# Mimi_layout_logo.net
KiCad netlist of a schematic drawn in EAGLE
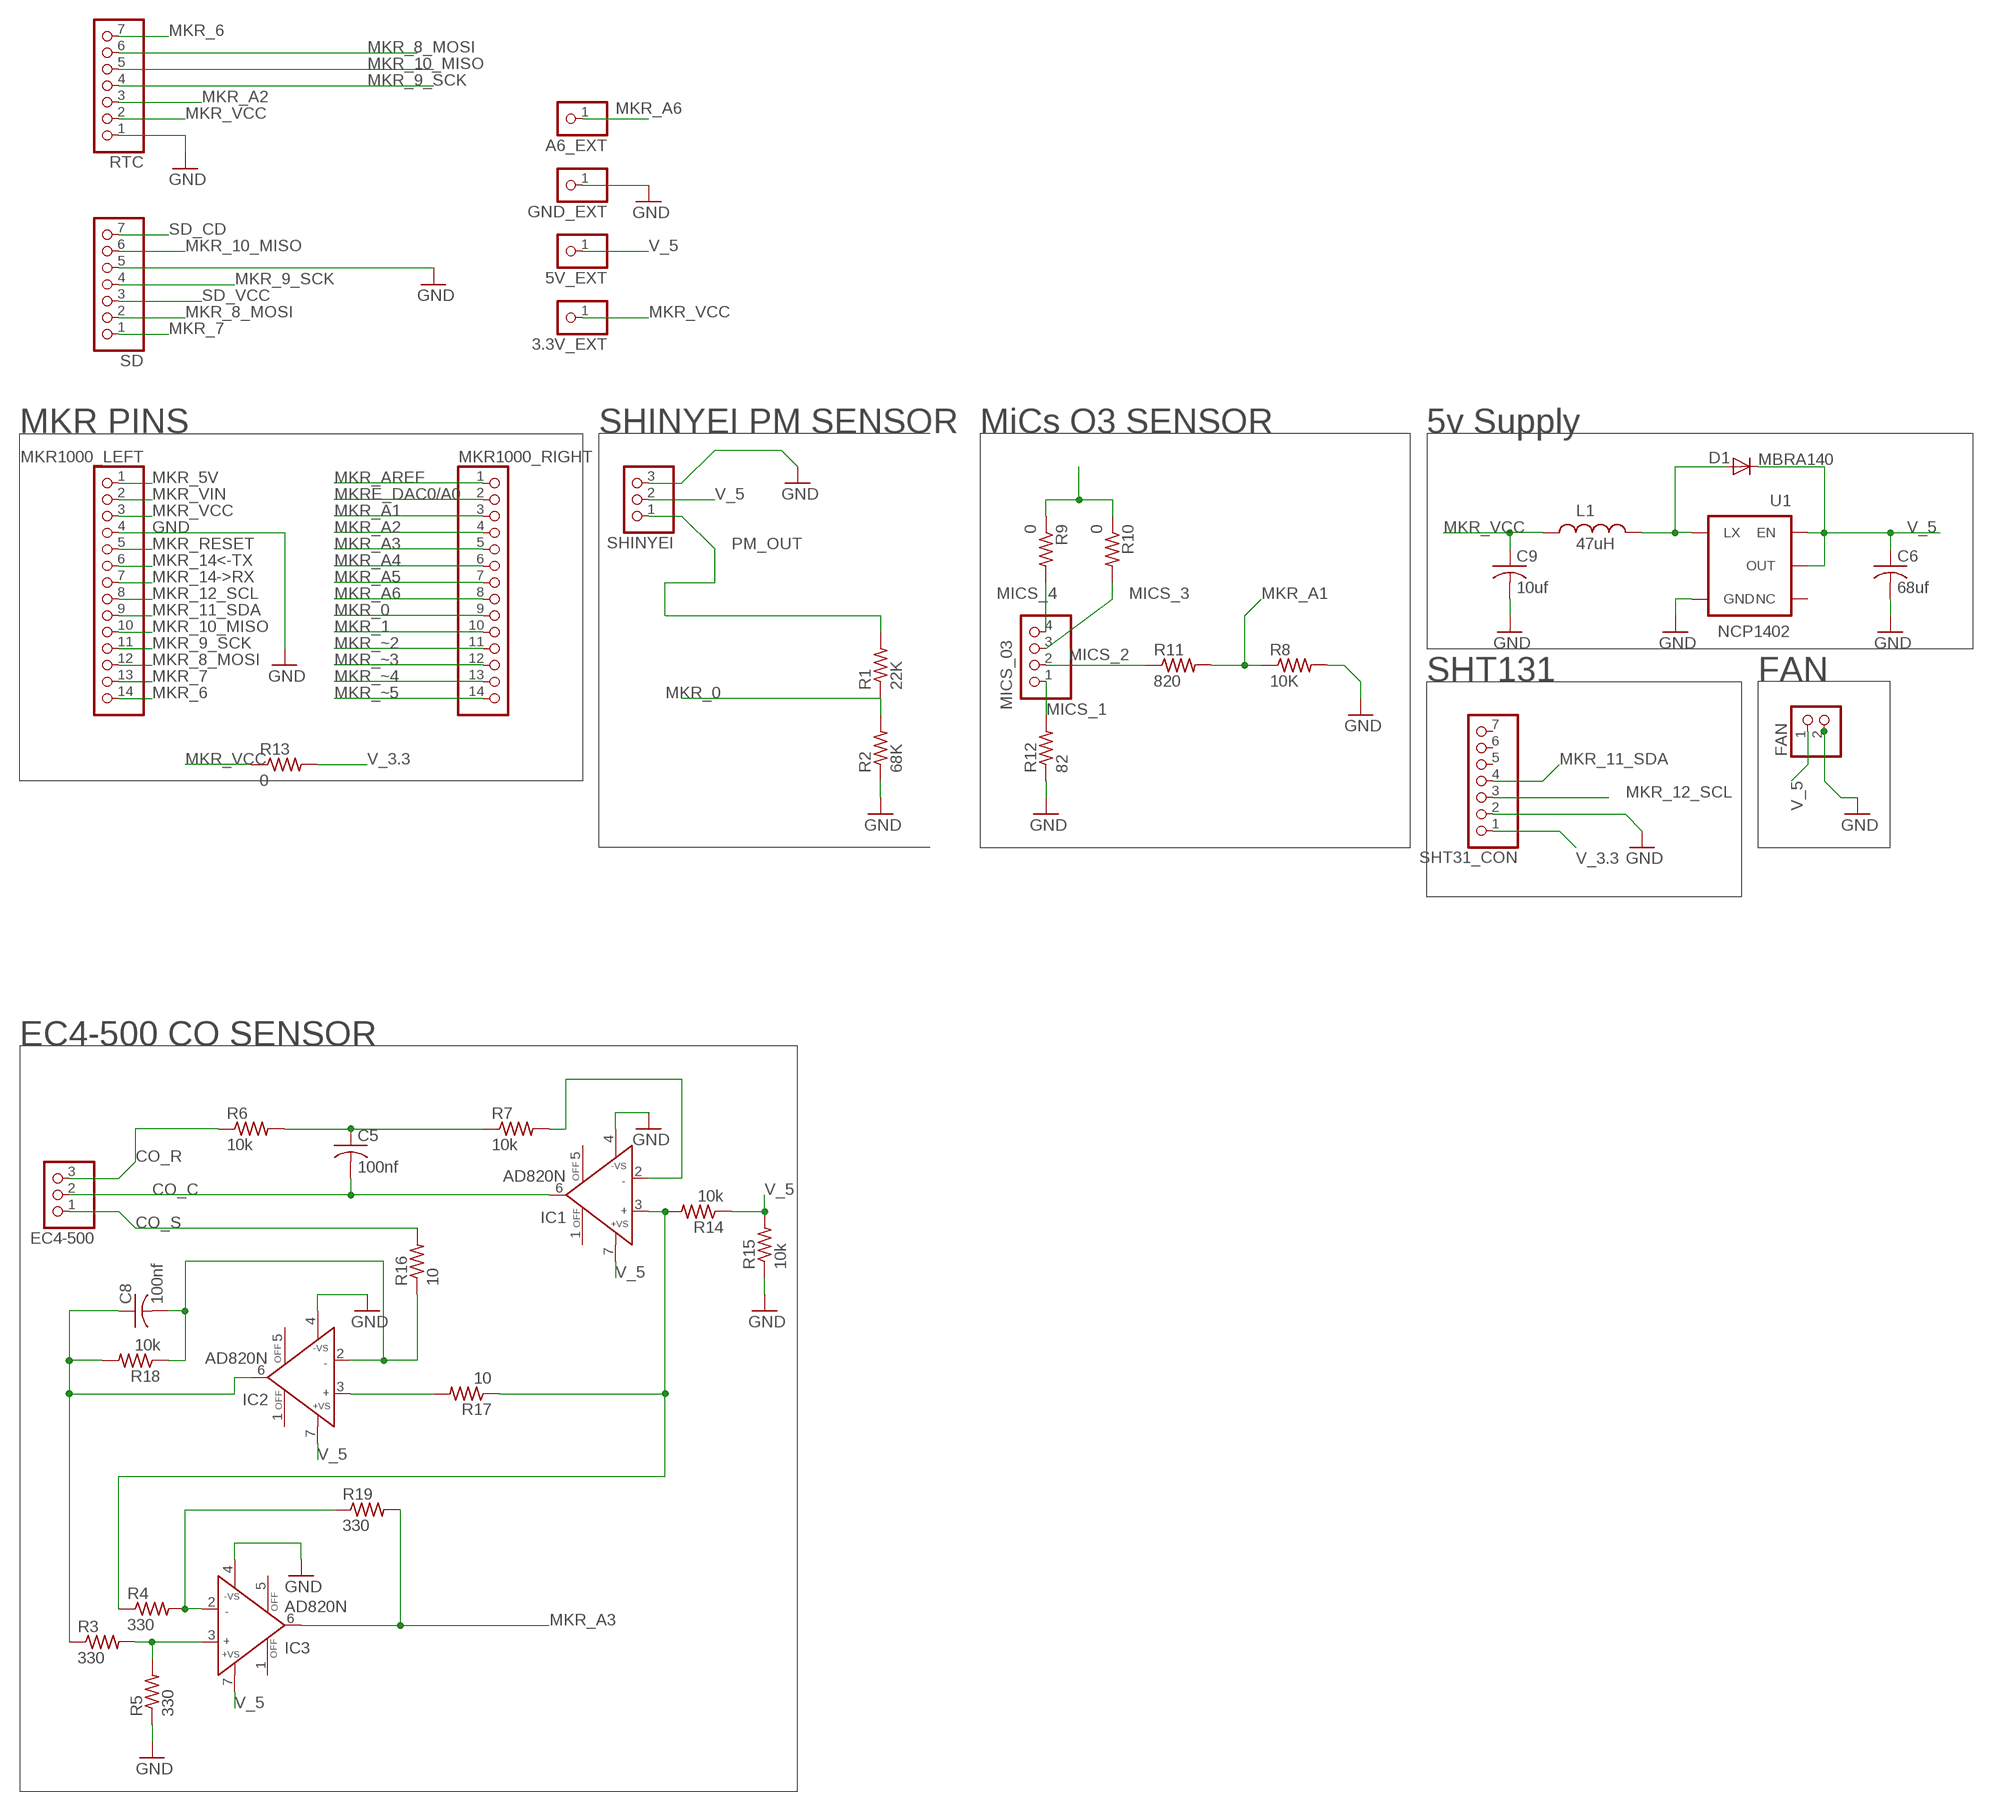
[diagram p0: schematic, sheet 1]

(export (version "E")
  (design (tool "Eeschema 10.0.6"))
  (components
    (comp (ref "3.3V_EXT")
      (value "PINHD-1X1")
      (footprint "eagle-import:1X01")
      (libsource (lib "eagle-import") (part "PINHD-1X1"))
    )
    (comp (ref "5V_EXT")
      (value "PINHD-1X1")
      (footprint "eagle-import:1X01")
      (libsource (lib "eagle-import") (part "PINHD-1X1"))
    )
    (comp (ref "A6_EXT")
      (value "PINHD-1X1")
      (footprint "eagle-import:1X01")
      (libsource (lib "eagle-import") (part "PINHD-1X1"))
    )
    (comp (ref "C5")
      (value "100nf")
      (footprint "eagle-import:C0805")
      (libsource (lib "eagle-import") (part "C-USC0805"))
    )
    (comp (ref "C6")
      (value "68uf")
      (footprint "eagle-import:C0805")
      (libsource (lib "eagle-import") (part "C-USC0805"))
    )
    (comp (ref "C8")
      (value "100nf")
      (footprint "eagle-import:C0805")
      (libsource (lib "eagle-import") (part "C-USC0805"))
    )
    (comp (ref "C9")
      (value "10uf")
      (footprint "eagle-import:C0805")
      (libsource (lib "eagle-import") (part "C-USC0805"))
    )
    (comp (ref "D1")
      (value "MBRA140")
      (footprint "eagle-import:SMA-DIODE")
      (libsource (lib "eagle-import") (part "DIODESMA"))
    )
    (comp (ref "EC4-500")
      (value "PINHD-1X3")
      (footprint "eagle-import:1X03")
      (libsource (lib "eagle-import") (part "PINHD-1X3"))
    )
    (comp (ref "FAN")
      (value "PINHD-1X2")
      (footprint "eagle-import:1X02")
      (libsource (lib "eagle-import") (part "PINHD-1X2"))
    )
    (comp (ref "GND_EXT")
      (value "PINHD-1X1")
      (footprint "eagle-import:1X01")
      (libsource (lib "eagle-import") (part "PINHD-1X1"))
    )
    (comp (ref "IC1")
      (value "AD820N")
      (footprint "eagle-import:DIL08")
      (libsource (lib "eagle-import") (part "AD820N"))
    )
    (comp (ref "IC2")
      (value "AD820N")
      (footprint "eagle-import:DIL08")
      (libsource (lib "eagle-import") (part "AD820N"))
    )
    (comp (ref "IC3")
      (value "AD820N")
      (footprint "eagle-import:DIL08")
      (libsource (lib "eagle-import") (part "AD820N"))
    )
    (comp (ref "L1")
      (value "47uH")
      (footprint "eagle-import:CR54")
      (libsource (lib "eagle-import") (part "INDUCTORCR54"))
    )
    (comp (ref "MICS_03")
      (value "PINHD-1X4")
      (footprint "eagle-import:1X04")
      (libsource (lib "eagle-import") (part "PINHD-1X4"))
    )
    (comp (ref "MKR1000_LEFT")
      (value "PINHD-1X14")
      (footprint "eagle-import:1X14")
      (libsource (lib "eagle-import") (part "PINHD-1X14"))
    )
    (comp (ref "MKR1000_RIGHT")
      (value "PINHD-1X14")
      (footprint "eagle-import:1X14")
      (libsource (lib "eagle-import") (part "PINHD-1X14"))
    )
    (comp (ref "R1")
      (value "22K")
      (footprint "eagle-import:R0805")
      (libsource (lib "eagle-import") (part "R-US_R0805"))
    )
    (comp (ref "R2")
      (value "68K")
      (footprint "eagle-import:R0805")
      (libsource (lib "eagle-import") (part "R-US_R0805"))
    )
    (comp (ref "R3")
      (value "330")
      (footprint "eagle-import:R0805")
      (libsource (lib "eagle-import") (part "R-US_R0805"))
    )
    (comp (ref "R4")
      (value "330")
      (footprint "eagle-import:R0805")
      (libsource (lib "eagle-import") (part "R-US_R0805"))
    )
    (comp (ref "R5")
      (value "330")
      (footprint "eagle-import:R0805")
      (libsource (lib "eagle-import") (part "R-US_R0805"))
    )
    (comp (ref "R6")
      (value "10k")
      (footprint "eagle-import:R0805")
      (libsource (lib "eagle-import") (part "R-US_R0805"))
    )
    (comp (ref "R7")
      (value "10k")
      (footprint "eagle-import:R0805")
      (libsource (lib "eagle-import") (part "R-US_R0805"))
    )
    (comp (ref "R8")
      (value "10K")
      (footprint "eagle-import:R0805")
      (libsource (lib "eagle-import") (part "R-US_R0805"))
    )
    (comp (ref "R9")
      (value "0")
      (footprint "eagle-import:R0805")
      (libsource (lib "eagle-import") (part "R-US_R0805"))
    )
    (comp (ref "R10")
      (value "0")
      (footprint "eagle-import:R0805")
      (libsource (lib "eagle-import") (part "R-US_R0805"))
    )
    (comp (ref "R11")
      (value "820")
      (footprint "eagle-import:R0805")
      (libsource (lib "eagle-import") (part "R-US_R0805"))
    )
    (comp (ref "R12")
      (value "82")
      (footprint "eagle-import:R0805")
      (libsource (lib "eagle-import") (part "R-US_R0805"))
    )
    (comp (ref "R13")
      (value "0")
      (footprint "eagle-import:R0805")
      (libsource (lib "eagle-import") (part "R-US_R0805"))
    )
    (comp (ref "R14")
      (value "10k")
      (footprint "eagle-import:R0805")
      (libsource (lib "eagle-import") (part "R-US_R0805"))
    )
    (comp (ref "R15")
      (value "10k")
      (footprint "eagle-import:R0805")
      (libsource (lib "eagle-import") (part "R-US_R0805"))
    )
    (comp (ref "R16")
      (value "10")
      (footprint "eagle-import:R0805")
      (libsource (lib "eagle-import") (part "R-US_R0805"))
    )
    (comp (ref "R17")
      (value "10")
      (footprint "eagle-import:R0805")
      (libsource (lib "eagle-import") (part "R-US_R0805"))
    )
    (comp (ref "R18")
      (value "10k")
      (footprint "eagle-import:R0805")
      (libsource (lib "eagle-import") (part "R-US_R0805"))
    )
    (comp (ref "R19")
      (value "330")
      (footprint "eagle-import:R0805")
      (libsource (lib "eagle-import") (part "R-US_R0805"))
    )
    (comp (ref "RTC")
      (value "PINHD-1X7")
      (footprint "eagle-import:1X07")
      (libsource (lib "eagle-import") (part "PINHD-1X7"))
    )
    (comp (ref "SD")
      (value "PINHD-1X7")
      (footprint "eagle-import:1X07")
      (libsource (lib "eagle-import") (part "PINHD-1X7"))
    )
    (comp (ref "SHINYEI")
      (value "PINHD-1X3")
      (footprint "eagle-import:1X03")
      (libsource (lib "eagle-import") (part "PINHD-1X3"))
    )
    (comp (ref "SHT31_CON")
      (value "PINHD-1X7")
      (footprint "eagle-import:1X07")
      (libsource (lib "eagle-import") (part "PINHD-1X7"))
    )
    (comp (ref "U1")
      (value "NCP1402")
      (footprint "eagle-import:SOT23-5")
      (libsource (lib "eagle-import") (part "V_REG_NCP1400SOT23-5"))
    )
  )
  (nets
    (net (code "1") (name "/CO_C") (class "Default")
      (node (ref "C5") (pin "2") (pinfunction "2_2") (pintype "passive"))
      (node (ref "EC4-500") (pin "2") (pinfunction "2_2") (pintype "passive"))
      (node (ref "IC1") (pin "6") (pinfunction "OUT_6") (pintype "output"))
    )
    (net (code "2") (name "/CO_R") (class "Default")
      (node (ref "EC4-500") (pin "3") (pinfunction "3_3") (pintype "passive"))
      (node (ref "R6") (pin "1") (pinfunction "1_1") (pintype "passive"))
    )
    (net (code "3") (name "/CO_S") (class "Default")
      (node (ref "EC4-500") (pin "1") (pinfunction "1_1") (pintype "passive"))
      (node (ref "R16") (pin "2") (pinfunction "2_2") (pintype "passive"))
    )
    (net (code "4") (name "/MICS_1") (class "Default")
      (node (ref "MICS_03") (pin "1") (pinfunction "1_1") (pintype "passive"))
      (node (ref "R12") (pin "2") (pinfunction "2_2") (pintype "passive"))
    )
    (net (code "5") (name "/MICS_2") (class "Default")
      (node (ref "MICS_03") (pin "2") (pinfunction "2_2") (pintype "passive"))
      (node (ref "R11") (pin "1") (pinfunction "1_1") (pintype "passive"))
    )
    (net (code "6") (name "/MICS_3") (class "Default")
      (node (ref "MICS_03") (pin "3") (pinfunction "3_3") (pintype "passive"))
      (node (ref "R10") (pin "2") (pinfunction "2_2") (pintype "passive"))
    )
    (net (code "7") (name "/MICS_4") (class "Default")
      (node (ref "MICS_03") (pin "4") (pinfunction "4_4") (pintype "passive"))
      (node (ref "R9") (pin "2") (pinfunction "2_2") (pintype "passive"))
    )
    (net (code "8") (name "/MKRE_DAC0{slash}A0") (class "Default")
      (node (ref "MKR1000_RIGHT") (pin "2") (pinfunction "2_2") (pintype "passive"))
    )
    (net (code "9") (name "/MKR_0") (class "Default")
      (node (ref "MKR1000_RIGHT") (pin "9") (pinfunction "9_9") (pintype "passive"))
      (node (ref "R1") (pin "1") (pinfunction "1_1") (pintype "passive"))
      (node (ref "R2") (pin "2") (pinfunction "2_2") (pintype "passive"))
    )
    (net (code "10") (name "/MKR_1") (class "Default")
      (node (ref "MKR1000_RIGHT") (pin "10") (pinfunction "10_10") (pintype "passive"))
    )
    (net (code "11") (name "/MKR_5V") (class "Default")
      (node (ref "MKR1000_LEFT") (pin "1") (pinfunction "1_1") (pintype "passive"))
    )
    (net (code "12") (name "/MKR_6") (class "Default")
      (node (ref "MKR1000_LEFT") (pin "14") (pinfunction "14_14") (pintype "passive"))
      (node (ref "RTC") (pin "7") (pinfunction "7_7") (pintype "passive"))
    )
    (net (code "13") (name "/MKR_7") (class "Default")
      (node (ref "MKR1000_LEFT") (pin "13") (pinfunction "13_13") (pintype "passive"))
      (node (ref "SD") (pin "1") (pinfunction "1_1") (pintype "passive"))
    )
    (net (code "14") (name "/MKR_8_MOSI") (class "Default")
      (node (ref "MKR1000_LEFT") (pin "12") (pinfunction "12_12") (pintype "passive"))
      (node (ref "RTC") (pin "6") (pinfunction "6_6") (pintype "passive"))
      (node (ref "SD") (pin "2") (pinfunction "2_2") (pintype "passive"))
    )
    (net (code "15") (name "/MKR_9_SCK") (class "Default")
      (node (ref "MKR1000_LEFT") (pin "11") (pinfunction "11_11") (pintype "passive"))
      (node (ref "RTC") (pin "4") (pinfunction "4_4") (pintype "passive"))
      (node (ref "SD") (pin "4") (pinfunction "4_4") (pintype "passive"))
    )
    (net (code "16") (name "/MKR_10_MISO") (class "Default")
      (node (ref "MKR1000_LEFT") (pin "10") (pinfunction "10_10") (pintype "passive"))
      (node (ref "RTC") (pin "5") (pinfunction "5_5") (pintype "passive"))
      (node (ref "SD") (pin "6") (pinfunction "6_6") (pintype "passive"))
    )
    (net (code "17") (name "/MKR_11_SDA") (class "Default")
      (node (ref "MKR1000_LEFT") (pin "9") (pinfunction "9_9") (pintype "passive"))
      (node (ref "SHT31_CON") (pin "4") (pinfunction "4_4") (pintype "passive"))
    )
    (net (code "18") (name "/MKR_12_SCL") (class "Default")
      (node (ref "MKR1000_LEFT") (pin "8") (pinfunction "8_8") (pintype "passive"))
      (node (ref "SHT31_CON") (pin "3") (pinfunction "3_3") (pintype "passive"))
    )
    (net (code "19") (name "/MKR_14->RX") (class "Default")
      (node (ref "MKR1000_LEFT") (pin "7") (pinfunction "7_7") (pintype "passive"))
    )
    (net (code "20") (name "/MKR_14<-TX") (class "Default")
      (node (ref "MKR1000_LEFT") (pin "6") (pinfunction "6_6") (pintype "passive"))
    )
    (net (code "21") (name "/MKR_A1") (class "Default")
      (node (ref "MKR1000_RIGHT") (pin "3") (pinfunction "3_3") (pintype "passive"))
      (node (ref "R11") (pin "2") (pinfunction "2_2") (pintype "passive"))
      (node (ref "R8") (pin "1") (pinfunction "1_1") (pintype "passive"))
    )
    (net (code "22") (name "/MKR_A2") (class "Default")
      (node (ref "MKR1000_RIGHT") (pin "4") (pinfunction "4_4") (pintype "passive"))
      (node (ref "RTC") (pin "3") (pinfunction "3_3") (pintype "passive"))
    )
    (net (code "23") (name "/MKR_A3") (class "Default")
      (node (ref "IC3") (pin "6") (pinfunction "OUT_6") (pintype "output"))
      (node (ref "MKR1000_RIGHT") (pin "5") (pinfunction "5_5") (pintype "passive"))
      (node (ref "R19") (pin "2") (pinfunction "2_2") (pintype "passive"))
    )
    (net (code "24") (name "/MKR_A4") (class "Default")
      (node (ref "MKR1000_RIGHT") (pin "6") (pinfunction "6_6") (pintype "passive"))
    )
    (net (code "25") (name "/MKR_A5") (class "Default")
      (node (ref "MKR1000_RIGHT") (pin "7") (pinfunction "7_7") (pintype "passive"))
    )
    (net (code "26") (name "/MKR_A6") (class "Default")
      (node (ref "A6_EXT") (pin "1") (pinfunction "1_1") (pintype "passive"))
      (node (ref "MKR1000_RIGHT") (pin "8") (pinfunction "8_8") (pintype "passive"))
    )
    (net (code "27") (name "/MKR_AREF") (class "Default")
      (node (ref "MKR1000_RIGHT") (pin "1") (pinfunction "1_1") (pintype "passive"))
    )
    (net (code "28") (name "/MKR_RESET") (class "Default")
      (node (ref "MKR1000_LEFT") (pin "5") (pinfunction "5_5") (pintype "passive"))
    )
    (net (code "29") (name "/MKR_VCC") (class "Default")
      (node (ref "3.3V_EXT") (pin "1") (pinfunction "1_1") (pintype "passive"))
      (node (ref "C9") (pin "1") (pinfunction "1_1") (pintype "passive"))
      (node (ref "L1") (pin "P$1") (pinfunction "1_P$1") (pintype "passive"))
      (node (ref "MKR1000_LEFT") (pin "3") (pinfunction "3_3") (pintype "passive"))
      (node (ref "R13") (pin "1") (pinfunction "1_1") (pintype "passive"))
      (node (ref "RTC") (pin "2") (pinfunction "2_2") (pintype "passive"))
    )
    (net (code "30") (name "/MKR_VIN") (class "Default")
      (node (ref "MKR1000_LEFT") (pin "2") (pinfunction "2_2") (pintype "passive"))
    )
    (net (code "31") (name "/MKR_~{2}") (class "Default")
      (node (ref "MKR1000_RIGHT") (pin "11") (pinfunction "11_11") (pintype "passive"))
    )
    (net (code "32") (name "/MKR_~{3}") (class "Default")
      (node (ref "MKR1000_RIGHT") (pin "12") (pinfunction "12_12") (pintype "passive"))
    )
    (net (code "33") (name "/MKR_~{4}") (class "Default")
      (node (ref "MKR1000_RIGHT") (pin "13") (pinfunction "13_13") (pintype "passive"))
    )
    (net (code "34") (name "/MKR_~{5}") (class "Default")
      (node (ref "MKR1000_RIGHT") (pin "14") (pinfunction "14_14") (pintype "passive"))
    )
    (net (code "35") (name "/PM_OUT") (class "Default")
      (node (ref "R1") (pin "2") (pinfunction "2_2") (pintype "passive"))
      (node (ref "SHINYEI") (pin "1") (pinfunction "1_1") (pintype "passive"))
    )
    (net (code "36") (name "/SD_CD") (class "Default")
      (node (ref "SD") (pin "7") (pinfunction "7_7") (pintype "passive"))
    )
    (net (code "37") (name "/SD_VCC") (class "Default")
      (node (ref "SD") (pin "3") (pinfunction "3_3") (pintype "passive"))
    )
    (net (code "38") (name "/V_3.3") (class "Default")
      (node (ref "R13") (pin "2") (pinfunction "2_2") (pintype "passive"))
      (node (ref "SHT31_CON") (pin "1") (pinfunction "1_1") (pintype "passive"))
    )
    (net (code "39") (name "/V_5") (class "Default")
      (node (ref "5V_EXT") (pin "1") (pinfunction "1_1") (pintype "passive"))
      (node (ref "C6") (pin "1") (pinfunction "1_1") (pintype "passive"))
      (node (ref "D1") (pin "C") (pinfunction "C_C") (pintype "passive"))
      (node (ref "FAN") (pin "1") (pinfunction "1_1") (pintype "passive"))
      (node (ref "IC1") (pin "7") (pinfunction "+VS_7") (pintype "input"))
      (node (ref "IC2") (pin "7") (pinfunction "+VS_7") (pintype "input"))
      (node (ref "IC3") (pin "7") (pinfunction "+VS_7") (pintype "input"))
      (node (ref "R10") (pin "1") (pinfunction "1_1") (pintype "passive"))
      (node (ref "R14") (pin "1") (pinfunction "1_1") (pintype "passive"))
      (node (ref "R15") (pin "2") (pinfunction "2_2") (pintype "passive"))
      (node (ref "R9") (pin "1") (pinfunction "1_1") (pintype "passive"))
      (node (ref "SHINYEI") (pin "2") (pinfunction "2_2") (pintype "passive"))
      (node (ref "U1") (pin "1") (pinfunction "EN_1") (pintype "input"))
      (node (ref "U1") (pin "2") (pinfunction "OUT_2") (pintype "passive"))
    )
    (net (code "40") (name "GND") (class "Default")
      (node (ref "C6") (pin "2") (pinfunction "2_2") (pintype "passive"))
      (node (ref "C9") (pin "2") (pinfunction "2_2") (pintype "passive"))
      (node (ref "FAN") (pin "2") (pinfunction "2_2") (pintype "passive"))
      (node (ref "GND_EXT") (pin "1") (pinfunction "1_1") (pintype "passive"))
      (node (ref "IC1") (pin "4") (pinfunction "-VS_4") (pintype "input"))
      (node (ref "IC2") (pin "4") (pinfunction "-VS_4") (pintype "input"))
      (node (ref "IC3") (pin "4") (pinfunction "-VS_4") (pintype "input"))
      (node (ref "MKR1000_LEFT") (pin "4") (pinfunction "4_4") (pintype "passive"))
      (node (ref "R12") (pin "1") (pinfunction "1_1") (pintype "passive"))
      (node (ref "R15") (pin "1") (pinfunction "1_1") (pintype "passive"))
      (node (ref "R2") (pin "1") (pinfunction "1_1") (pintype "passive"))
      (node (ref "R5") (pin "1") (pinfunction "1_1") (pintype "passive"))
      (node (ref "R8") (pin "2") (pinfunction "2_2") (pintype "passive"))
      (node (ref "RTC") (pin "1") (pinfunction "1_1") (pintype "passive"))
      (node (ref "SD") (pin "5") (pinfunction "5_5") (pintype "passive"))
      (node (ref "SHINYEI") (pin "3") (pinfunction "3_3") (pintype "passive"))
      (node (ref "SHT31_CON") (pin "2") (pinfunction "2_2") (pintype "passive"))
      (node (ref "U1") (pin "4") (pinfunction "GND_4") (pintype "input"))
    )
    (net (code "41") (name "Net-(C5-Pad1)") (class "Default")
      (node (ref "C5") (pin "1") (pinfunction "1_1") (pintype "passive"))
      (node (ref "R6") (pin "2") (pinfunction "2_2") (pintype "passive"))
      (node (ref "R7") (pin "1") (pinfunction "1_1") (pintype "passive"))
    )
    (net (code "42") (name "Net-(IC1-IN+)") (class "Default")
      (node (ref "IC1") (pin "3") (pinfunction "IN+_3") (pintype "input"))
      (node (ref "R14") (pin "2") (pinfunction "2_2") (pintype "passive"))
      (node (ref "R17") (pin "1") (pinfunction "1_1") (pintype "passive"))
      (node (ref "R4") (pin "1") (pinfunction "1_1") (pintype "passive"))
    )
    (net (code "43") (name "Net-(IC1-IN-)") (class "Default")
      (node (ref "IC1") (pin "2") (pinfunction "IN-_2") (pintype "input"))
      (node (ref "R7") (pin "2") (pinfunction "2_2") (pintype "passive"))
    )
    (net (code "44") (name "Net-(IC2-IN+)") (class "Default")
      (node (ref "IC2") (pin "3") (pinfunction "IN+_3") (pintype "input"))
      (node (ref "R17") (pin "2") (pinfunction "2_2") (pintype "passive"))
    )
    (net (code "45") (name "Net-(IC2-IN-)") (class "Default")
      (node (ref "C8") (pin "2") (pinfunction "2_2") (pintype "passive"))
      (node (ref "IC2") (pin "2") (pinfunction "IN-_2") (pintype "input"))
      (node (ref "R16") (pin "1") (pinfunction "1_1") (pintype "passive"))
      (node (ref "R18") (pin "1") (pinfunction "1_1") (pintype "passive"))
    )
    (net (code "46") (name "Net-(IC2-OUT)") (class "Default")
      (node (ref "C8") (pin "1") (pinfunction "1_1") (pintype "passive"))
      (node (ref "IC2") (pin "6") (pinfunction "OUT_6") (pintype "output"))
      (node (ref "R18") (pin "2") (pinfunction "2_2") (pintype "passive"))
      (node (ref "R3") (pin "1") (pinfunction "1_1") (pintype "passive"))
    )
    (net (code "47") (name "Net-(IC3-IN+)") (class "Default")
      (node (ref "IC3") (pin "3") (pinfunction "IN+_3") (pintype "input"))
      (node (ref "R3") (pin "2") (pinfunction "2_2") (pintype "passive"))
      (node (ref "R5") (pin "2") (pinfunction "2_2") (pintype "passive"))
    )
    (net (code "48") (name "Net-(IC3-IN-)") (class "Default")
      (node (ref "IC3") (pin "2") (pinfunction "IN-_2") (pintype "input"))
      (node (ref "R19") (pin "1") (pinfunction "1_1") (pintype "passive"))
      (node (ref "R4") (pin "2") (pinfunction "2_2") (pintype "passive"))
    )
    (net (code "49") (name "Net-(L1-2)") (class "Default")
      (node (ref "D1") (pin "A") (pinfunction "A_A") (pintype "passive"))
      (node (ref "L1") (pin "P$2") (pinfunction "2_P$2") (pintype "passive"))
      (node (ref "U1") (pin "5") (pinfunction "LX_5") (pintype "input"))
    )
    (net (code "50") (name "unconnected-(IC1-OFF-Pad1)") (class "Default")
      (node (ref "IC1") (pin "1") (pinfunction "OFF_1") (pintype "passive"))
    )
    (net (code "51") (name "unconnected-(IC1-OFF-Pad5)") (class "Default")
      (node (ref "IC1") (pin "5") (pinfunction "OFF_5") (pintype "passive"))
    )
    (net (code "52") (name "unconnected-(IC2-OFF-Pad1)") (class "Default")
      (node (ref "IC2") (pin "1") (pinfunction "OFF_1") (pintype "passive"))
    )
    (net (code "53") (name "unconnected-(IC2-OFF-Pad5)") (class "Default")
      (node (ref "IC2") (pin "5") (pinfunction "OFF_5") (pintype "passive"))
    )
    (net (code "54") (name "unconnected-(IC3-OFF-Pad1)") (class "Default")
      (node (ref "IC3") (pin "1") (pinfunction "OFF_1") (pintype "passive"))
    )
    (net (code "55") (name "unconnected-(IC3-OFF-Pad5)") (class "Default")
      (node (ref "IC3") (pin "5") (pinfunction "OFF_5") (pintype "passive"))
    )
    (net (code "56") (name "unconnected-(SHT31_CON-Pad5)") (class "Default")
      (node (ref "SHT31_CON") (pin "5") (pinfunction "5_5") (pintype "passive"))
    )
    (net (code "57") (name "unconnected-(SHT31_CON-Pad6)") (class "Default")
      (node (ref "SHT31_CON") (pin "6") (pinfunction "6_6") (pintype "passive"))
    )
    (net (code "58") (name "unconnected-(SHT31_CON-Pad7)") (class "Default")
      (node (ref "SHT31_CON") (pin "7") (pinfunction "7_7") (pintype "passive"))
    )
    (net (code "59") (name "unconnected-(U1-NC-Pad3)") (class "Default")
      (node (ref "U1") (pin "3") (pinfunction "NC_3") (pintype "input"))
    )
  )
)
